# STM32F103_V2.net
KiCad netlist of a schematic drawn in EAGLE
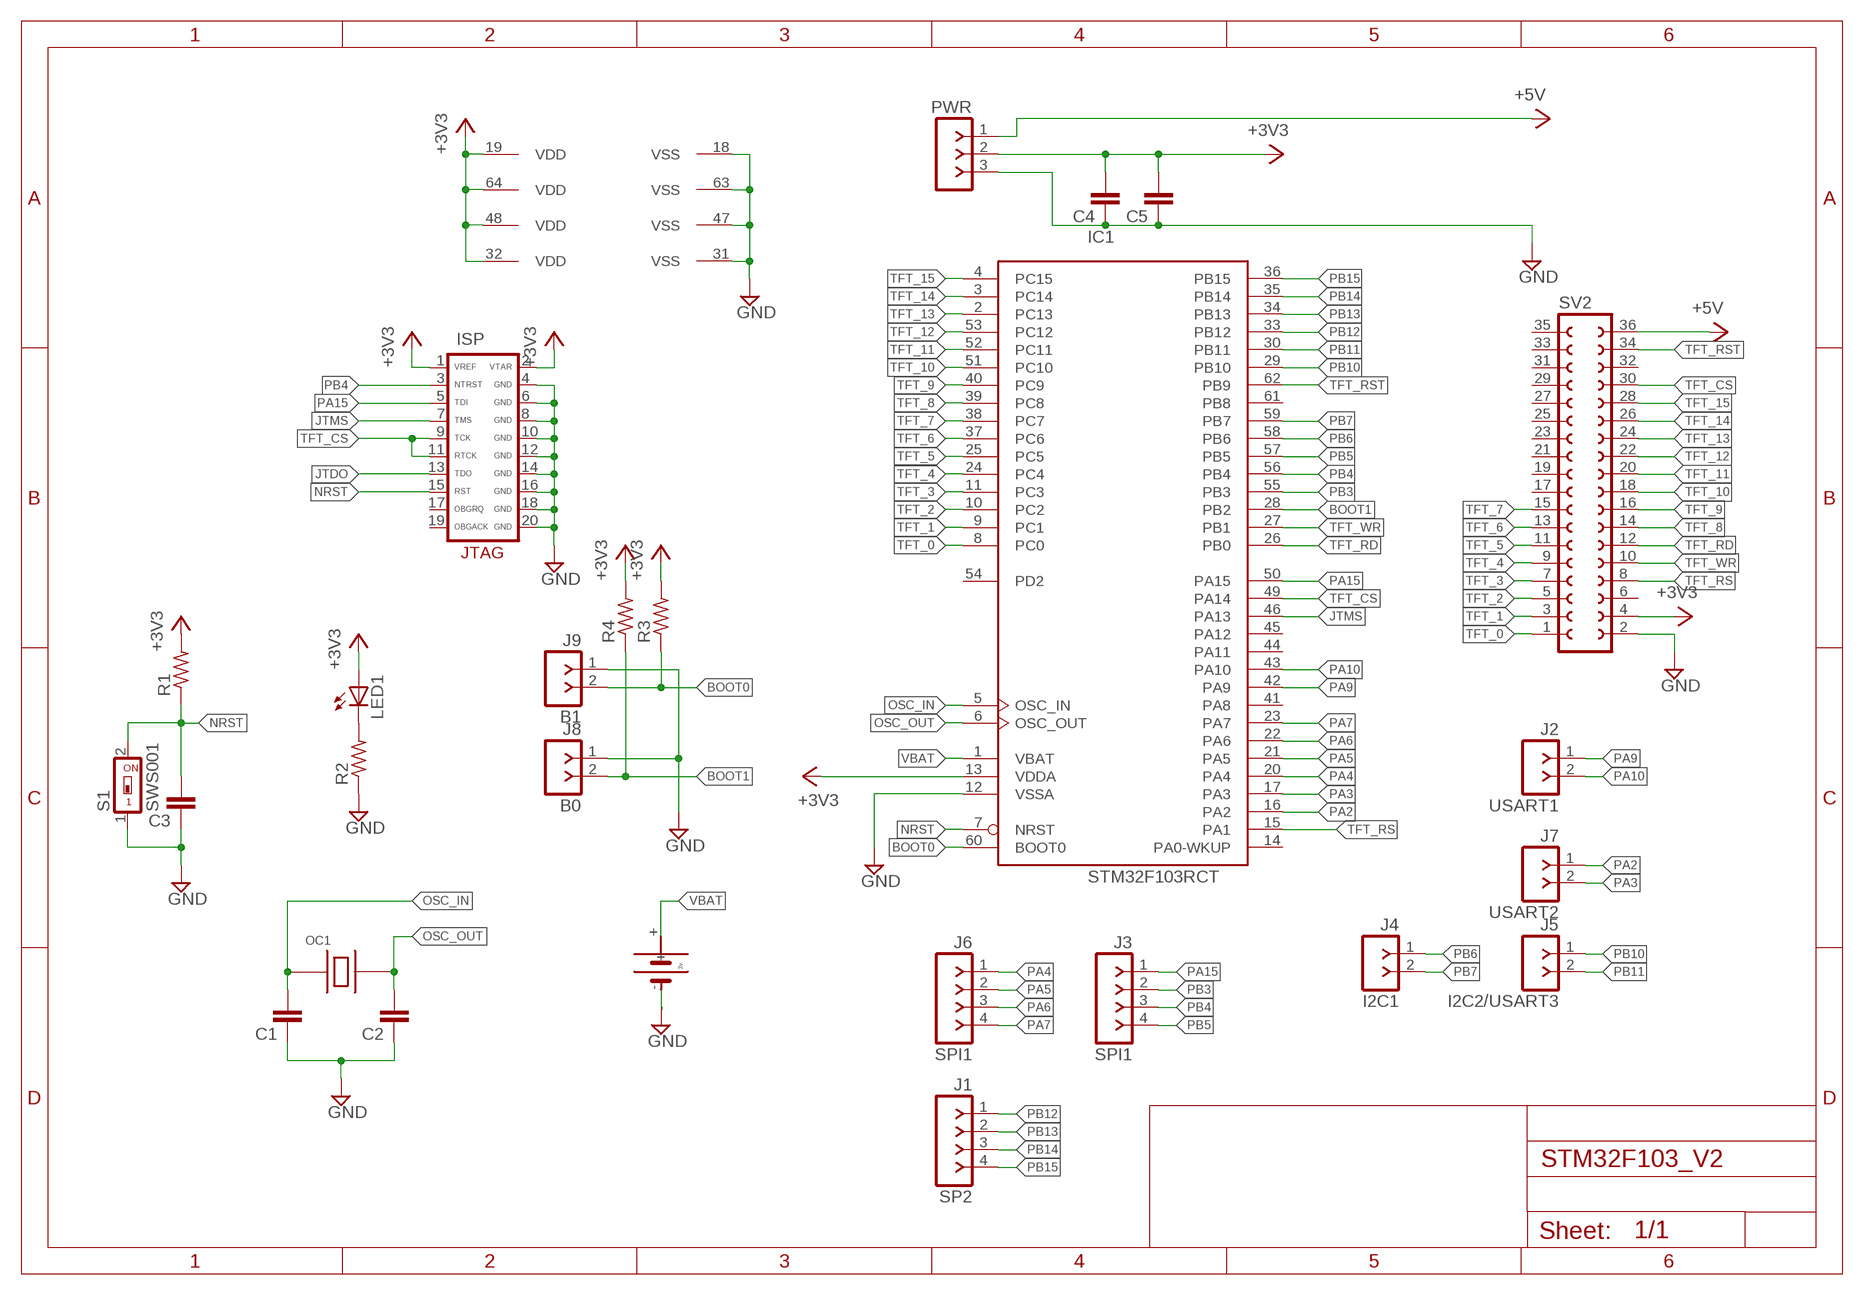
[diagram p0: schematic, sheet 1]

(export (version "E")
  (design (tool "Eeschema 10.0.6"))
  (components
    (comp (ref "C1")
      (value "C-EUC1206")
      (footprint "eagle-import:C1206")
      (libsource (lib "eagle-import") (part "C-EUC1206"))
    )
    (comp (ref "C2")
      (value "C-EUC1206")
      (footprint "eagle-import:C1206")
      (libsource (lib "eagle-import") (part "C-EUC1206"))
    )
    (comp (ref "C3")
      (value "C-EUC1206")
      (footprint "eagle-import:C1206")
      (libsource (lib "eagle-import") (part "C-EUC1206"))
    )
    (comp (ref "C4")
      (value "C-EUC1206")
      (footprint "eagle-import:C1206")
      (libsource (lib "eagle-import") (part "C-EUC1206"))
    )
    (comp (ref "C5")
      (value "C-EUC1206")
      (footprint "eagle-import:C1206")
      (libsource (lib "eagle-import") (part "C-EUC1206"))
    )
    (comp (ref "IC1")
      (value "STM32F103RCT")
      (footprint "eagle-import:LQFP64")
      (libsource (lib "eagle-import") (part "STM32F103RTC"))
    )
    (comp (ref "ISP")
      (value "JTAG")
      (footprint "eagle-import:PAK100_2500-20")
      (libsource (lib "eagle-import") (part "JTAG-ARM-PAK100/2500-20"))
    )
    (comp (ref "J1")
      (value "SP2")
      (footprint "eagle-import:SIP-100-04-40")
      (libsource (lib "eagle-import") (part "F-1X04-SIP-100-40"))
    )
    (comp (ref "J2")
      (value "USART1")
      (footprint "eagle-import:SIP-100-02-40")
      (libsource (lib "eagle-import") (part "F-1X02-SIP-100-40"))
    )
    (comp (ref "J3")
      (value "SPI1")
      (footprint "eagle-import:SIP-100-04-40")
      (libsource (lib "eagle-import") (part "F-1X04-SIP-100-40"))
    )
    (comp (ref "J4")
      (value "I2C1")
      (footprint "eagle-import:SIP-100-02-40")
      (libsource (lib "eagle-import") (part "F-1X02-SIP-100-40"))
    )
    (comp (ref "J5")
      (value "I2C2/USART3")
      (footprint "eagle-import:SIP-100-02-40")
      (libsource (lib "eagle-import") (part "F-1X02-SIP-100-40"))
    )
    (comp (ref "J6")
      (value "SPI1")
      (footprint "eagle-import:SIP-100-04-40")
      (libsource (lib "eagle-import") (part "F-1X04-SIP-100-40"))
    )
    (comp (ref "J7")
      (value "USART2")
      (footprint "eagle-import:SIP-100-02-40")
      (libsource (lib "eagle-import") (part "F-1X02-SIP-100-40"))
    )
    (comp (ref "J8")
      (value "B0")
      (footprint "eagle-import:SIP-100-02-40")
      (libsource (lib "eagle-import") (part "F-1X02-SIP-100-40"))
    )
    (comp (ref "J9")
      (value "B1")
      (footprint "eagle-import:SIP-100-02-40")
      (libsource (lib "eagle-import") (part "F-1X02-SIP-100-40"))
    )
    (comp (ref "LED1")
      (value "LEDSML1206")
      (footprint "eagle-import:SML1206")
      (libsource (lib "eagle-import") (part "LEDSML1206"))
    )
    (comp (ref "OC1")
      (value "SMAQ-7050B")
      (footprint "eagle-import:IQG7050B")
      (libsource (lib "eagle-import") (part "SMAQ-7050B"))
    )
    (comp (ref "PWR")
      (value "F-1X03-SIP-100-40")
      (footprint "eagle-import:SIP-100-03-40")
      (libsource (lib "eagle-import") (part "F-1X03-SIP-100-40"))
    )
    (comp (ref "R1")
      (value "R-US_R1206")
      (footprint "eagle-import:R1206")
      (libsource (lib "eagle-import") (part "R-US_R1206"))
    )
    (comp (ref "R2")
      (value "R-US_R1206")
      (footprint "eagle-import:R1206")
      (libsource (lib "eagle-import") (part "R-US_R1206"))
    )
    (comp (ref "R3")
      (value "R-US_R1206")
      (footprint "eagle-import:R1206")
      (libsource (lib "eagle-import") (part "R-US_R1206"))
    )
    (comp (ref "R4")
      (value "R-US_R1206")
      (footprint "eagle-import:R1206")
      (libsource (lib "eagle-import") (part "R-US_R1206"))
    )
    (comp (ref "S1")
      (value "SWS001")
      (footprint "eagle-import:SMS-001")
      (libsource (lib "eagle-import") (part "SWS001"))
    )
    (comp (ref "SV2")
      (value "FE18-2")
      (footprint "eagle-import:FE18-2")
      (libsource (lib "eagle-import") (part "FE18-2"))
    )
    (comp (ref "U$2")
      (value "1220BATTERY_SF")
      (footprint "eagle-import:1220BATTERY")
      (libsource (lib "eagle-import") (part "1220BATTERY_SF"))
    )
  )
  (nets
    (net (code "1") (name "+3V3") (class "Default")
      (node (ref "C4") (pin "2") (pinfunction "2_2") (pintype "passive"))
      (node (ref "C5") (pin "2") (pinfunction "2_2") (pintype "passive"))
      (node (ref "IC1") (pin "13") (pinfunction "VDDA_13") (pintype "power_in"))
      (node (ref "IC1") (pin "19") (pinfunction "VDD_19") (pintype "power_in"))
      (node (ref "IC1") (pin "32") (pinfunction "VDD_32") (pintype "power_in"))
      (node (ref "IC1") (pin "48") (pinfunction "VDD_48") (pintype "power_in"))
      (node (ref "IC1") (pin "64") (pinfunction "VDD_64") (pintype "power_in"))
      (node (ref "ISP") (pin "1") (pinfunction "VREF_1") (pintype "passive"))
      (node (ref "ISP") (pin "2") (pinfunction "VTAR_2") (pintype "passive"))
      (node (ref "LED1") (pin "A") (pinfunction "A_A") (pintype "passive"))
      (node (ref "PWR") (pin "2") (pinfunction "2_2") (pintype "passive"))
      (node (ref "R1") (pin "2") (pinfunction "2_2") (pintype "passive"))
      (node (ref "R3") (pin "2") (pinfunction "2_2") (pintype "passive"))
      (node (ref "R4") (pin "2") (pinfunction "2_2") (pintype "passive"))
      (node (ref "SV2") (pin "4") (pinfunction "4_4") (pintype "passive"))
    )
    (net (code "2") (name "+5V") (class "Default")
      (node (ref "PWR") (pin "1") (pinfunction "1_1") (pintype "passive"))
      (node (ref "SV2") (pin "36") (pinfunction "36_36") (pintype "passive"))
    )
    (net (code "3") (name "BOOT0") (class "Default")
      (node (ref "IC1") (pin "60") (pinfunction "BOOT0_60") (pintype "input"))
      (node (ref "J9") (pin "2") (pinfunction "2_2") (pintype "passive"))
      (node (ref "R3") (pin "1") (pinfunction "1_1") (pintype "passive"))
    )
    (net (code "4") (name "BOOT1") (class "Default")
      (node (ref "IC1") (pin "28") (pinfunction "PB2_28") (pintype "bidirectional"))
      (node (ref "J8") (pin "2") (pinfunction "2_2") (pintype "passive"))
      (node (ref "R4") (pin "1") (pinfunction "1_1") (pintype "passive"))
    )
    (net (code "5") (name "GND") (class "Default")
      (node (ref "C1") (pin "1") (pinfunction "1_1") (pintype "passive"))
      (node (ref "C2") (pin "1") (pinfunction "1_1") (pintype "passive"))
      (node (ref "C3") (pin "1") (pinfunction "1_1") (pintype "passive"))
      (node (ref "C4") (pin "1") (pinfunction "1_1") (pintype "passive"))
      (node (ref "C5") (pin "1") (pinfunction "1_1") (pintype "passive"))
      (node (ref "IC1") (pin "12") (pinfunction "VSSA_12") (pintype "power_in"))
      (node (ref "IC1") (pin "18") (pinfunction "VSS_18") (pintype "power_in"))
      (node (ref "IC1") (pin "31") (pinfunction "VSS_31") (pintype "power_in"))
      (node (ref "IC1") (pin "47") (pinfunction "VSS_47") (pintype "power_in"))
      (node (ref "IC1") (pin "63") (pinfunction "VSS_63") (pintype "power_in"))
      (node (ref "ISP") (pin "10") (pinfunction "GND_10") (pintype "passive"))
      (node (ref "ISP") (pin "12") (pinfunction "GND_12") (pintype "passive"))
      (node (ref "ISP") (pin "14") (pinfunction "GND_14") (pintype "passive"))
      (node (ref "ISP") (pin "16") (pinfunction "GND_16") (pintype "passive"))
      (node (ref "ISP") (pin "18") (pinfunction "GND_18") (pintype "passive"))
      (node (ref "ISP") (pin "20") (pinfunction "GND_20") (pintype "passive"))
      (node (ref "ISP") (pin "4") (pinfunction "GND_4") (pintype "passive"))
      (node (ref "ISP") (pin "6") (pinfunction "GND_6") (pintype "passive"))
      (node (ref "ISP") (pin "8") (pinfunction "GND_8") (pintype "passive"))
      (node (ref "J8") (pin "1") (pinfunction "1_1") (pintype "passive"))
      (node (ref "J9") (pin "1") (pinfunction "1_1") (pintype "passive"))
      (node (ref "PWR") (pin "3") (pinfunction "3_3") (pintype "passive"))
      (node (ref "R2") (pin "1") (pinfunction "1_1") (pintype "passive"))
      (node (ref "S1") (pin "1") (pinfunction "1_1") (pintype "passive"))
      (node (ref "SV2") (pin "2") (pinfunction "2_2") (pintype "passive"))
      (node (ref "U$2") (pin "-") (pinfunction "-_-") (pintype "bidirectional"))
    )
    (net (code "6") (name "JTDO") (class "Default")
      (node (ref "ISP") (pin "13") (pinfunction "TDO_13") (pintype "passive"))
    )
    (net (code "7") (name "JTMS") (class "Default")
      (node (ref "IC1") (pin "46") (pinfunction "PA13_46") (pintype "bidirectional"))
      (node (ref "ISP") (pin "7") (pinfunction "TMS_7") (pintype "passive"))
    )
    (net (code "8") (name "NRST") (class "Default")
      (node (ref "C3") (pin "2") (pinfunction "2_2") (pintype "passive"))
      (node (ref "IC1") (pin "7") (pinfunction "NRST_7") (pintype "bidirectional"))
      (node (ref "ISP") (pin "15") (pinfunction "RST_15") (pintype "passive"))
      (node (ref "R1") (pin "1") (pinfunction "1_1") (pintype "passive"))
      (node (ref "S1") (pin "2") (pinfunction "2_2") (pintype "passive"))
    )
    (net (code "9") (name "Net-(LED1-PadC)") (class "Default")
      (node (ref "LED1") (pin "C") (pinfunction "C_C") (pintype "passive"))
      (node (ref "R2") (pin "2") (pinfunction "2_2") (pintype "passive"))
    )
    (net (code "10") (name "OSC_IN") (class "Default")
      (node (ref "C1") (pin "2") (pinfunction "2_2") (pintype "passive"))
      (node (ref "IC1") (pin "5") (pinfunction "OSC_IN_5") (pintype "bidirectional"))
      (node (ref "OC1") (pin "P$1") (pinfunction "PIN1_P$1") (pintype "bidirectional"))
    )
    (net (code "11") (name "OSC_OUT") (class "Default")
      (node (ref "C2") (pin "2") (pinfunction "2_2") (pintype "passive"))
      (node (ref "IC1") (pin "6") (pinfunction "OSC_OUT_6") (pintype "bidirectional"))
      (node (ref "OC1") (pin "P$3") (pinfunction "PIN2_P$3") (pintype "bidirectional"))
    )
    (net (code "12") (name "PA2") (class "Default")
      (node (ref "IC1") (pin "16") (pinfunction "PA2_16") (pintype "bidirectional"))
      (node (ref "J7") (pin "1") (pinfunction "1_1") (pintype "passive"))
    )
    (net (code "13") (name "PA3") (class "Default")
      (node (ref "IC1") (pin "17") (pinfunction "PA3_17") (pintype "bidirectional"))
      (node (ref "J7") (pin "2") (pinfunction "2_2") (pintype "passive"))
    )
    (net (code "14") (name "PA4") (class "Default")
      (node (ref "IC1") (pin "20") (pinfunction "PA4_20") (pintype "bidirectional"))
      (node (ref "J6") (pin "1") (pinfunction "1_1") (pintype "passive"))
    )
    (net (code "15") (name "PA5") (class "Default")
      (node (ref "IC1") (pin "21") (pinfunction "PA5_21") (pintype "bidirectional"))
      (node (ref "J6") (pin "2") (pinfunction "2_2") (pintype "passive"))
    )
    (net (code "16") (name "PA6") (class "Default")
      (node (ref "IC1") (pin "22") (pinfunction "PA6_22") (pintype "bidirectional"))
      (node (ref "J6") (pin "3") (pinfunction "3_3") (pintype "passive"))
    )
    (net (code "17") (name "PA7") (class "Default")
      (node (ref "IC1") (pin "23") (pinfunction "PA7_23") (pintype "bidirectional"))
      (node (ref "J6") (pin "4") (pinfunction "4_4") (pintype "passive"))
    )
    (net (code "18") (name "PA9") (class "Default")
      (node (ref "IC1") (pin "42") (pinfunction "PA9_42") (pintype "bidirectional"))
      (node (ref "J2") (pin "1") (pinfunction "1_1") (pintype "passive"))
    )
    (net (code "19") (name "PA10") (class "Default")
      (node (ref "IC1") (pin "43") (pinfunction "PA10_43") (pintype "bidirectional"))
      (node (ref "J2") (pin "2") (pinfunction "2_2") (pintype "passive"))
    )
    (net (code "20") (name "PA15") (class "Default")
      (node (ref "IC1") (pin "50") (pinfunction "PA15_50") (pintype "bidirectional"))
      (node (ref "ISP") (pin "5") (pinfunction "TDI_5") (pintype "passive"))
      (node (ref "J3") (pin "1") (pinfunction "1_1") (pintype "passive"))
    )
    (net (code "21") (name "PB3") (class "Default")
      (node (ref "IC1") (pin "55") (pinfunction "PB3_55") (pintype "bidirectional"))
      (node (ref "J3") (pin "2") (pinfunction "2_2") (pintype "passive"))
    )
    (net (code "22") (name "PB4") (class "Default")
      (node (ref "IC1") (pin "56") (pinfunction "PB4_56") (pintype "bidirectional"))
      (node (ref "ISP") (pin "3") (pinfunction "NTRST_3") (pintype "passive"))
      (node (ref "J3") (pin "3") (pinfunction "3_3") (pintype "passive"))
    )
    (net (code "23") (name "PB5") (class "Default")
      (node (ref "IC1") (pin "57") (pinfunction "PB5_57") (pintype "bidirectional"))
      (node (ref "J3") (pin "4") (pinfunction "4_4") (pintype "passive"))
    )
    (net (code "24") (name "PB6") (class "Default")
      (node (ref "IC1") (pin "58") (pinfunction "PB6_58") (pintype "bidirectional"))
      (node (ref "J4") (pin "1") (pinfunction "1_1") (pintype "passive"))
    )
    (net (code "25") (name "PB7") (class "Default")
      (node (ref "IC1") (pin "59") (pinfunction "PB7_59") (pintype "bidirectional"))
      (node (ref "J4") (pin "2") (pinfunction "2_2") (pintype "passive"))
    )
    (net (code "26") (name "PB10") (class "Default")
      (node (ref "IC1") (pin "29") (pinfunction "PB10_29") (pintype "bidirectional"))
      (node (ref "J5") (pin "1") (pinfunction "1_1") (pintype "passive"))
    )
    (net (code "27") (name "PB11") (class "Default")
      (node (ref "IC1") (pin "30") (pinfunction "PB11_30") (pintype "bidirectional"))
      (node (ref "J5") (pin "2") (pinfunction "2_2") (pintype "passive"))
    )
    (net (code "28") (name "PB12") (class "Default")
      (node (ref "IC1") (pin "33") (pinfunction "PB12_33") (pintype "bidirectional"))
      (node (ref "J1") (pin "1") (pinfunction "1_1") (pintype "passive"))
    )
    (net (code "29") (name "PB13") (class "Default")
      (node (ref "IC1") (pin "34") (pinfunction "PB13_34") (pintype "bidirectional"))
      (node (ref "J1") (pin "2") (pinfunction "2_2") (pintype "passive"))
    )
    (net (code "30") (name "PB14") (class "Default")
      (node (ref "IC1") (pin "35") (pinfunction "PB14_35") (pintype "bidirectional"))
      (node (ref "J1") (pin "3") (pinfunction "3_3") (pintype "passive"))
    )
    (net (code "31") (name "PB15") (class "Default")
      (node (ref "IC1") (pin "36") (pinfunction "PB15_36") (pintype "bidirectional"))
      (node (ref "J1") (pin "4") (pinfunction "4_4") (pintype "passive"))
    )
    (net (code "32") (name "TFT_0") (class "Default")
      (node (ref "IC1") (pin "8") (pinfunction "PC0_8") (pintype "bidirectional"))
      (node (ref "SV2") (pin "1") (pinfunction "1_1") (pintype "passive"))
    )
    (net (code "33") (name "TFT_1") (class "Default")
      (node (ref "IC1") (pin "9") (pinfunction "PC1_9") (pintype "bidirectional"))
      (node (ref "SV2") (pin "3") (pinfunction "3_3") (pintype "passive"))
    )
    (net (code "34") (name "TFT_2") (class "Default")
      (node (ref "IC1") (pin "10") (pinfunction "PC2_10") (pintype "bidirectional"))
      (node (ref "SV2") (pin "5") (pinfunction "5_5") (pintype "passive"))
    )
    (net (code "35") (name "TFT_3") (class "Default")
      (node (ref "IC1") (pin "11") (pinfunction "PC3_11") (pintype "bidirectional"))
      (node (ref "SV2") (pin "7") (pinfunction "7_7") (pintype "passive"))
    )
    (net (code "36") (name "TFT_4") (class "Default")
      (node (ref "IC1") (pin "24") (pinfunction "PC4_24") (pintype "bidirectional"))
      (node (ref "SV2") (pin "9") (pinfunction "9_9") (pintype "passive"))
    )
    (net (code "37") (name "TFT_5") (class "Default")
      (node (ref "IC1") (pin "25") (pinfunction "PC5_25") (pintype "bidirectional"))
      (node (ref "SV2") (pin "11") (pinfunction "11_11") (pintype "passive"))
    )
    (net (code "38") (name "TFT_6") (class "Default")
      (node (ref "IC1") (pin "37") (pinfunction "PC6_37") (pintype "bidirectional"))
      (node (ref "SV2") (pin "13") (pinfunction "13_13") (pintype "passive"))
    )
    (net (code "39") (name "TFT_7") (class "Default")
      (node (ref "IC1") (pin "38") (pinfunction "PC7_38") (pintype "bidirectional"))
      (node (ref "SV2") (pin "15") (pinfunction "15_15") (pintype "passive"))
    )
    (net (code "40") (name "TFT_8") (class "Default")
      (node (ref "IC1") (pin "39") (pinfunction "PC8_39") (pintype "bidirectional"))
      (node (ref "SV2") (pin "14") (pinfunction "14_14") (pintype "passive"))
    )
    (net (code "41") (name "TFT_9") (class "Default")
      (node (ref "IC1") (pin "40") (pinfunction "PC9_40") (pintype "bidirectional"))
      (node (ref "SV2") (pin "16") (pinfunction "16_16") (pintype "passive"))
    )
    (net (code "42") (name "TFT_10") (class "Default")
      (node (ref "IC1") (pin "51") (pinfunction "PC10_51") (pintype "bidirectional"))
      (node (ref "SV2") (pin "18") (pinfunction "18_18") (pintype "passive"))
    )
    (net (code "43") (name "TFT_11") (class "Default")
      (node (ref "IC1") (pin "52") (pinfunction "PC11_52") (pintype "bidirectional"))
      (node (ref "SV2") (pin "20") (pinfunction "20_20") (pintype "passive"))
    )
    (net (code "44") (name "TFT_12") (class "Default")
      (node (ref "IC1") (pin "53") (pinfunction "PC12_53") (pintype "bidirectional"))
      (node (ref "SV2") (pin "22") (pinfunction "22_22") (pintype "passive"))
    )
    (net (code "45") (name "TFT_13") (class "Default")
      (node (ref "IC1") (pin "2") (pinfunction "PC13_2") (pintype "bidirectional"))
      (node (ref "SV2") (pin "24") (pinfunction "24_24") (pintype "passive"))
    )
    (net (code "46") (name "TFT_14") (class "Default")
      (node (ref "IC1") (pin "3") (pinfunction "PC14_3") (pintype "bidirectional"))
      (node (ref "SV2") (pin "26") (pinfunction "26_26") (pintype "passive"))
    )
    (net (code "47") (name "TFT_15") (class "Default")
      (node (ref "IC1") (pin "4") (pinfunction "PC15_4") (pintype "bidirectional"))
      (node (ref "SV2") (pin "28") (pinfunction "28_28") (pintype "passive"))
    )
    (net (code "48") (name "TFT_CS") (class "Default")
      (node (ref "IC1") (pin "49") (pinfunction "PA14_49") (pintype "bidirectional"))
      (node (ref "ISP") (pin "11") (pinfunction "RTCK_11") (pintype "passive"))
      (node (ref "ISP") (pin "9") (pinfunction "TCK_9") (pintype "passive"))
      (node (ref "SV2") (pin "30") (pinfunction "30_30") (pintype "passive"))
    )
    (net (code "49") (name "TFT_RD") (class "Default")
      (node (ref "IC1") (pin "26") (pinfunction "PB0_26") (pintype "bidirectional"))
      (node (ref "SV2") (pin "12") (pinfunction "12_12") (pintype "passive"))
    )
    (net (code "50") (name "TFT_RS") (class "Default")
      (node (ref "IC1") (pin "15") (pinfunction "PA1_15") (pintype "bidirectional"))
      (node (ref "SV2") (pin "8") (pinfunction "8_8") (pintype "passive"))
    )
    (net (code "51") (name "TFT_RST") (class "Default")
      (node (ref "IC1") (pin "62") (pinfunction "PB9_62") (pintype "bidirectional"))
      (node (ref "SV2") (pin "34") (pinfunction "34_34") (pintype "passive"))
    )
    (net (code "52") (name "TFT_WR") (class "Default")
      (node (ref "IC1") (pin "27") (pinfunction "PB1_27") (pintype "bidirectional"))
      (node (ref "SV2") (pin "10") (pinfunction "10_10") (pintype "passive"))
    )
    (net (code "53") (name "VBAT") (class "Default")
      (node (ref "IC1") (pin "1") (pinfunction "VBAT_1") (pintype "power_in"))
      (node (ref "U$2") (pin "+") (pinfunction "+_+") (pintype "bidirectional"))
    )
    (net (code "54") (name "unconnected-(IC1A-PA0-WKUP-Pad14)") (class "Default")
      (node (ref "IC1") (pin "14") (pinfunction "PA0-WKUP_14") (pintype "bidirectional"))
    )
    (net (code "55") (name "unconnected-(IC1A-PA8-Pad41)") (class "Default")
      (node (ref "IC1") (pin "41") (pinfunction "PA8_41") (pintype "bidirectional"))
    )
    (net (code "56") (name "unconnected-(IC1A-PA11-Pad44)") (class "Default")
      (node (ref "IC1") (pin "44") (pinfunction "PA11_44") (pintype "bidirectional"))
    )
    (net (code "57") (name "unconnected-(IC1A-PA12-Pad45)") (class "Default")
      (node (ref "IC1") (pin "45") (pinfunction "PA12_45") (pintype "bidirectional"))
    )
    (net (code "58") (name "unconnected-(IC1A-PB8-Pad61)") (class "Default")
      (node (ref "IC1") (pin "61") (pinfunction "PB8_61") (pintype "bidirectional"))
    )
    (net (code "59") (name "unconnected-(IC1A-PD2-Pad54)") (class "Default")
      (node (ref "IC1") (pin "54") (pinfunction "PD2_54") (pintype "bidirectional"))
    )
    (net (code "60") (name "unconnected-(ISP-OBGACK-Pad19)") (class "Default")
      (node (ref "ISP") (pin "19") (pinfunction "OBGACK_19") (pintype "passive"))
    )
    (net (code "61") (name "unconnected-(ISP-OBGRQ-Pad17)") (class "Default")
      (node (ref "ISP") (pin "17") (pinfunction "OBGRQ_17") (pintype "passive"))
    )
    (net (code "62") (name "unconnected-(SV2-Pad6)") (class "Default")
      (node (ref "SV2") (pin "6") (pinfunction "6_6") (pintype "passive"))
    )
    (net (code "63") (name "unconnected-(SV2-Pad17)") (class "Default")
      (node (ref "SV2") (pin "17") (pinfunction "17_17") (pintype "passive"))
    )
    (net (code "64") (name "unconnected-(SV2-Pad19)") (class "Default")
      (node (ref "SV2") (pin "19") (pinfunction "19_19") (pintype "passive"))
    )
    (net (code "65") (name "unconnected-(SV2-Pad21)") (class "Default")
      (node (ref "SV2") (pin "21") (pinfunction "21_21") (pintype "passive"))
    )
    (net (code "66") (name "unconnected-(SV2-Pad23)") (class "Default")
      (node (ref "SV2") (pin "23") (pinfunction "23_23") (pintype "passive"))
    )
    (net (code "67") (name "unconnected-(SV2-Pad25)") (class "Default")
      (node (ref "SV2") (pin "25") (pinfunction "25_25") (pintype "passive"))
    )
    (net (code "68") (name "unconnected-(SV2-Pad27)") (class "Default")
      (node (ref "SV2") (pin "27") (pinfunction "27_27") (pintype "passive"))
    )
    (net (code "69") (name "unconnected-(SV2-Pad29)") (class "Default")
      (node (ref "SV2") (pin "29") (pinfunction "29_29") (pintype "passive"))
    )
    (net (code "70") (name "unconnected-(SV2-Pad31)") (class "Default")
      (node (ref "SV2") (pin "31") (pinfunction "31_31") (pintype "passive"))
    )
    (net (code "71") (name "unconnected-(SV2-Pad32)") (class "Default")
      (node (ref "SV2") (pin "32") (pinfunction "32_32") (pintype "passive"))
    )
    (net (code "72") (name "unconnected-(SV2-Pad33)") (class "Default")
      (node (ref "SV2") (pin "33") (pinfunction "33_33") (pintype "passive"))
    )
    (net (code "73") (name "unconnected-(SV2-Pad35)") (class "Default")
      (node (ref "SV2") (pin "35") (pinfunction "35_35") (pintype "passive"))
    )
  )
)
